# Sidewinder_Joystick_Buttonpad.net
KiCad netlist of a schematic drawn in EAGLE
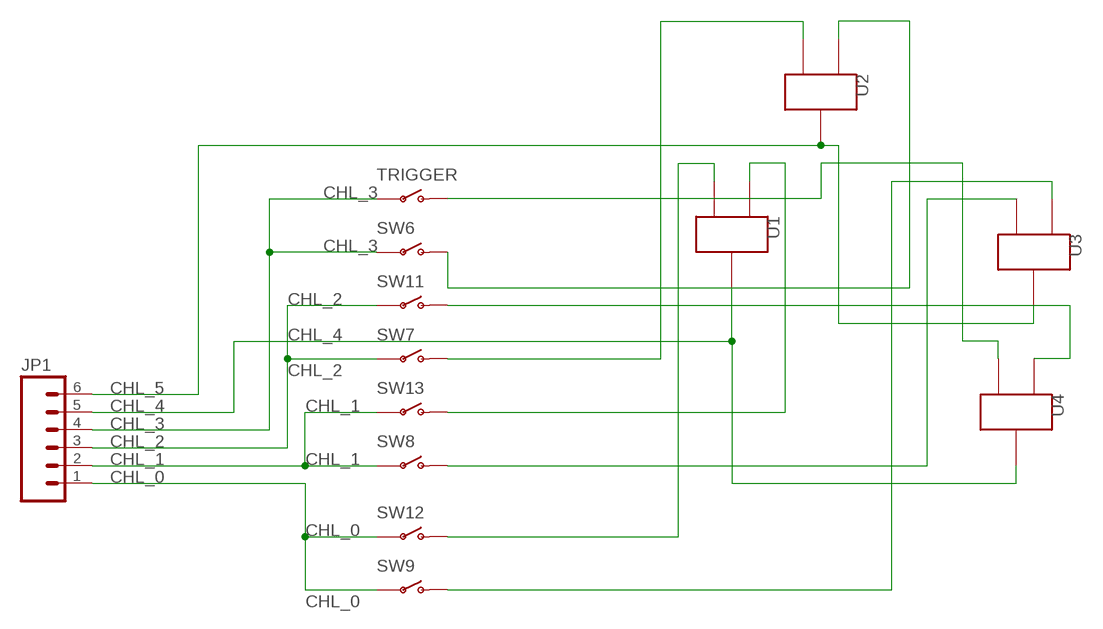
[diagram p0: schematic, sheet 1]

(export (version "E")
  (design (tool "Eeschema 10.0.6"))
  (components
    (comp (ref "JP1")
      (value "M06NO_SILK_FEMALE_PTH")
      (footprint "eagle-import:1X06_NO_SILK")
      (libsource (lib "eagle-import") (part "M06NO_SILK_FEMALE_PTH"))
    )
    (comp (ref "SW6")
      (value "SWITCH-SPST-2TV")
      (footprint "eagle-import:SWITCH-SPST-VERTICAL")
      (libsource (lib "eagle-import") (part "SWITCH-SPST-2TV"))
    )
    (comp (ref "SW7")
      (value "SWITCH-SPST-2TV")
      (footprint "eagle-import:SWITCH-SPST-VERTICAL")
      (libsource (lib "eagle-import") (part "SWITCH-SPST-2TV"))
    )
    (comp (ref "SW8")
      (value "SWITCH-SPST-2TV")
      (footprint "eagle-import:SWITCH-SPST-VERTICAL")
      (libsource (lib "eagle-import") (part "SWITCH-SPST-2TV"))
    )
    (comp (ref "SW9")
      (value "SWITCH-SPST-2TV")
      (footprint "eagle-import:SWITCH-SPST-VERTICAL")
      (libsource (lib "eagle-import") (part "SWITCH-SPST-2TV"))
    )
    (comp (ref "SW11")
      (value "SWITCH-SPST-2TV")
      (footprint "eagle-import:SWITCH-SPST-VERTICAL")
      (libsource (lib "eagle-import") (part "SWITCH-SPST-2TV"))
    )
    (comp (ref "SW12")
      (value "SWITCH-SPST-2TV")
      (footprint "eagle-import:SWITCH-SPST-VERTICAL")
      (libsource (lib "eagle-import") (part "SWITCH-SPST-2TV"))
    )
    (comp (ref "SW13")
      (value "SWITCH-SPST-2TV")
      (footprint "eagle-import:SWITCH-SPST-VERTICAL")
      (libsource (lib "eagle-import") (part "SWITCH-SPST-2TV"))
    )
    (comp (ref "TRIGGER")
      (value "SWITCH-SPST-2TV")
      (footprint "eagle-import:SWITCH-SPST-VERTICAL")
      (libsource (lib "eagle-import") (part "SWITCH-SPST-2TV"))
    )
    (comp (ref "U1")
      (value "MYSTERY-3-S0T23SOT23-3")
      (footprint "eagle-import:SOT23-3")
      (libsource (lib "eagle-import") (part "MYSTERY-3-S0T23SOT23-3"))
    )
    (comp (ref "U2")
      (value "MYSTERY-3-S0T23SOT23-3")
      (footprint "eagle-import:SOT23-3")
      (libsource (lib "eagle-import") (part "MYSTERY-3-S0T23SOT23-3"))
    )
    (comp (ref "U3")
      (value "MYSTERY-3-S0T23SOT23-3")
      (footprint "eagle-import:SOT23-3")
      (libsource (lib "eagle-import") (part "MYSTERY-3-S0T23SOT23-3"))
    )
    (comp (ref "U4")
      (value "MYSTERY-3-S0T23SOT23-3")
      (footprint "eagle-import:SOT23-3")
      (libsource (lib "eagle-import") (part "MYSTERY-3-S0T23SOT23-3"))
    )
  )
  (nets
    (net (code "1") (name "/CHL_0") (class "Default")
      (node (ref "JP1") (pin "1") (pinfunction "1_1") (pintype "passive"))
      (node (ref "SW12") (pin "2") (pinfunction "P_2") (pintype "passive"))
      (node (ref "SW9") (pin "2") (pinfunction "P_2") (pintype "passive"))
    )
    (net (code "2") (name "/CHL_1") (class "Default")
      (node (ref "JP1") (pin "2") (pinfunction "2_2") (pintype "passive"))
      (node (ref "SW13") (pin "2") (pinfunction "P_2") (pintype "passive"))
      (node (ref "SW8") (pin "2") (pinfunction "P_2") (pintype "passive"))
    )
    (net (code "3") (name "/CHL_2") (class "Default")
      (node (ref "JP1") (pin "3") (pinfunction "3_3") (pintype "passive"))
      (node (ref "SW11") (pin "2") (pinfunction "P_2") (pintype "passive"))
      (node (ref "SW7") (pin "2") (pinfunction "P_2") (pintype "passive"))
    )
    (net (code "4") (name "/CHL_3") (class "Default")
      (node (ref "JP1") (pin "4") (pinfunction "4_4") (pintype "passive"))
      (node (ref "SW6") (pin "2") (pinfunction "P_2") (pintype "passive"))
      (node (ref "TRIGGER") (pin "2") (pinfunction "P_2") (pintype "passive"))
    )
    (net (code "5") (name "/CHL_4") (class "Default")
      (node (ref "JP1") (pin "5") (pinfunction "5_5") (pintype "passive"))
      (node (ref "U1") (pin "2") (pinfunction "2_2") (pintype "bidirectional"))
      (node (ref "U4") (pin "2") (pinfunction "2_2") (pintype "bidirectional"))
    )
    (net (code "6") (name "/CHL_5") (class "Default")
      (node (ref "JP1") (pin "6") (pinfunction "6_6") (pintype "passive"))
      (node (ref "U2") (pin "2") (pinfunction "2_2") (pintype "bidirectional"))
      (node (ref "U3") (pin "2") (pinfunction "2_2") (pintype "bidirectional"))
    )
    (net (code "7") (name "Net-(SW6-O)") (class "Default")
      (node (ref "SW6") (pin "1") (pinfunction "O_1") (pintype "passive"))
      (node (ref "U2") (pin "1") (pinfunction "1_1") (pintype "bidirectional"))
    )
    (net (code "8") (name "Net-(SW7-O)") (class "Default")
      (node (ref "SW7") (pin "1") (pinfunction "O_1") (pintype "passive"))
      (node (ref "U2") (pin "3") (pinfunction "3_3") (pintype "bidirectional"))
    )
    (net (code "9") (name "Net-(SW8-O)") (class "Default")
      (node (ref "SW8") (pin "1") (pinfunction "O_1") (pintype "passive"))
      (node (ref "U3") (pin "3") (pinfunction "3_3") (pintype "bidirectional"))
    )
    (net (code "10") (name "Net-(SW9-O)") (class "Default")
      (node (ref "SW9") (pin "1") (pinfunction "O_1") (pintype "passive"))
      (node (ref "U3") (pin "1") (pinfunction "1_1") (pintype "bidirectional"))
    )
    (net (code "11") (name "Net-(SW11-O)") (class "Default")
      (node (ref "SW11") (pin "1") (pinfunction "O_1") (pintype "passive"))
      (node (ref "U4") (pin "1") (pinfunction "1_1") (pintype "bidirectional"))
    )
    (net (code "12") (name "Net-(SW12-O)") (class "Default")
      (node (ref "SW12") (pin "1") (pinfunction "O_1") (pintype "passive"))
      (node (ref "U1") (pin "3") (pinfunction "3_3") (pintype "bidirectional"))
    )
    (net (code "13") (name "Net-(SW13-O)") (class "Default")
      (node (ref "SW13") (pin "1") (pinfunction "O_1") (pintype "passive"))
      (node (ref "U1") (pin "1") (pinfunction "1_1") (pintype "bidirectional"))
    )
    (net (code "14") (name "Net-(TRIGGER-O)") (class "Default")
      (node (ref "TRIGGER") (pin "1") (pinfunction "O_1") (pintype "passive"))
      (node (ref "U4") (pin "3") (pinfunction "3_3") (pintype "bidirectional"))
    )
  )
)
